# videoselector_2_0v.net
KiCad netlist of a schematic drawn in EAGLE
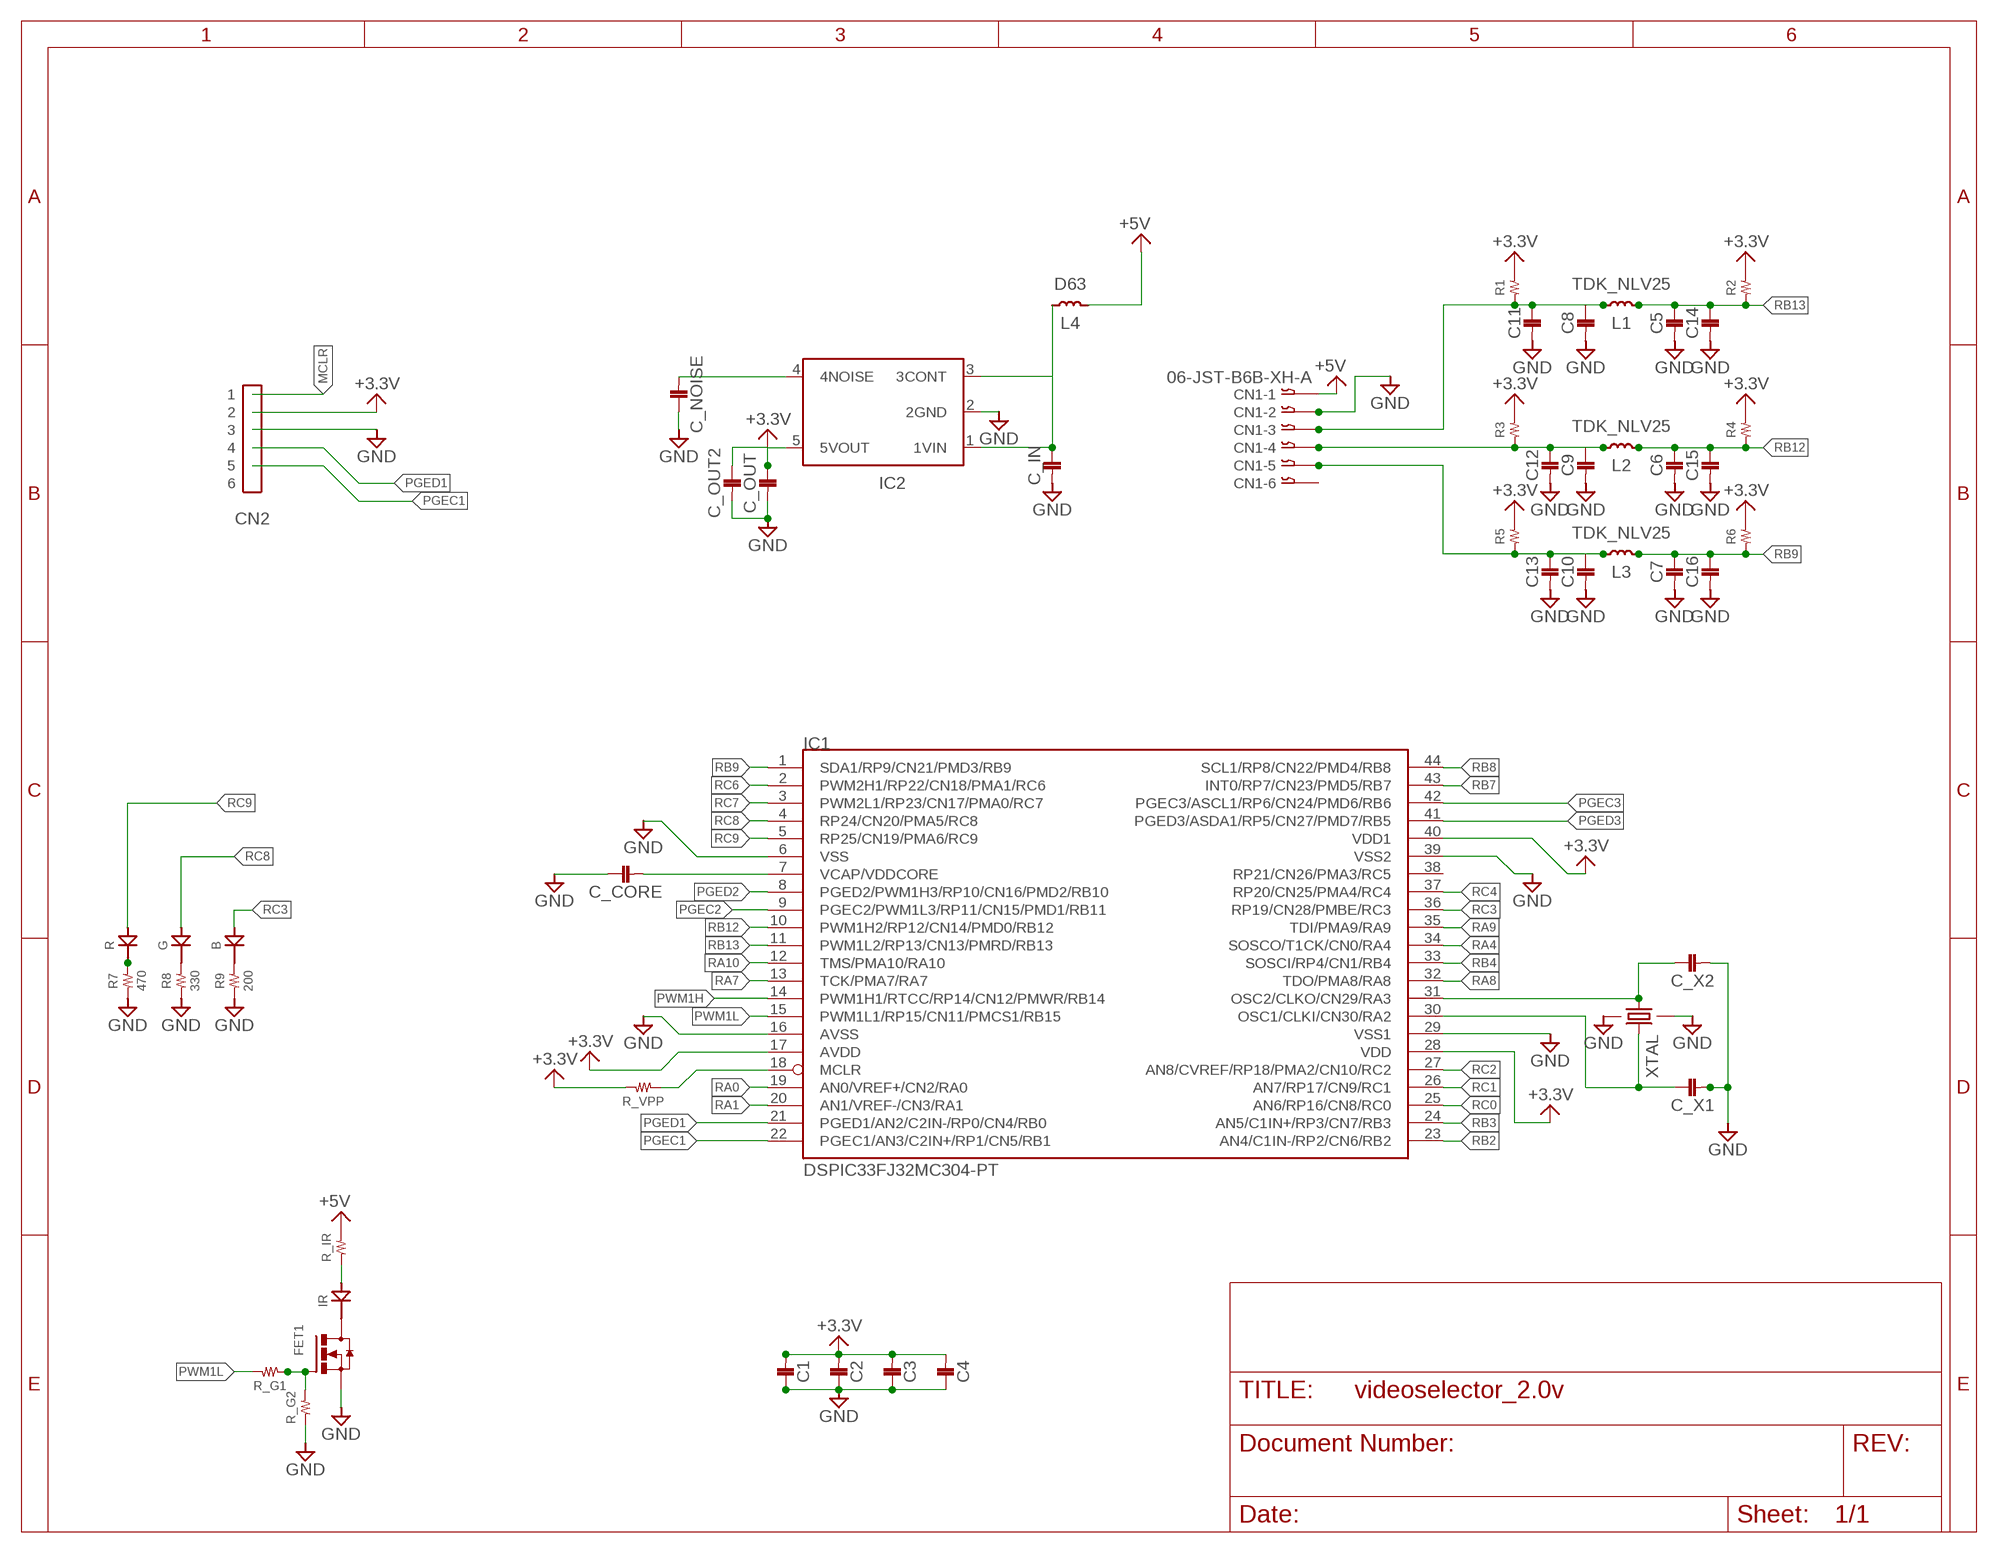
[diagram p0: schematic, sheet 1]

(export (version "E")
  (design (tool "Eeschema 10.0.6"))
  (components
    (comp (ref "B")
      (value "CHIPLED")
      (footprint "eagle-import:1608")
      (libsource (lib "eagle-import") (part "CHIPLED"))
    )
    (comp (ref "C1")
      (value "1608")
      (footprint "eagle-import:1608")
      (libsource (lib "eagle-import") (part "1608"))
    )
    (comp (ref "C2")
      (value "1608")
      (footprint "eagle-import:1608")
      (libsource (lib "eagle-import") (part "1608"))
    )
    (comp (ref "C3")
      (value "1608")
      (footprint "eagle-import:1608")
      (libsource (lib "eagle-import") (part "1608"))
    )
    (comp (ref "C4")
      (value "1608")
      (footprint "eagle-import:1608")
      (libsource (lib "eagle-import") (part "1608"))
    )
    (comp (ref "C5")
      (value "1608")
      (footprint "eagle-import:1608")
      (libsource (lib "eagle-import") (part "1608"))
    )
    (comp (ref "C6")
      (value "1608")
      (footprint "eagle-import:1608")
      (libsource (lib "eagle-import") (part "1608"))
    )
    (comp (ref "C7")
      (value "1608")
      (footprint "eagle-import:1608")
      (libsource (lib "eagle-import") (part "1608"))
    )
    (comp (ref "C8")
      (value "1608")
      (footprint "eagle-import:1608")
      (libsource (lib "eagle-import") (part "1608"))
    )
    (comp (ref "C9")
      (value "1608")
      (footprint "eagle-import:1608")
      (libsource (lib "eagle-import") (part "1608"))
    )
    (comp (ref "C10")
      (value "1608")
      (footprint "eagle-import:1608")
      (libsource (lib "eagle-import") (part "1608"))
    )
    (comp (ref "C11")
      (value "3225")
      (footprint "eagle-import:3225")
      (libsource (lib "eagle-import") (part "3225"))
    )
    (comp (ref "C12")
      (value "3225")
      (footprint "eagle-import:3225")
      (libsource (lib "eagle-import") (part "3225"))
    )
    (comp (ref "C13")
      (value "3225")
      (footprint "eagle-import:3225")
      (libsource (lib "eagle-import") (part "3225"))
    )
    (comp (ref "C14")
      (value "3225")
      (footprint "eagle-import:3225")
      (libsource (lib "eagle-import") (part "3225"))
    )
    (comp (ref "C15")
      (value "3225")
      (footprint "eagle-import:3225")
      (libsource (lib "eagle-import") (part "3225"))
    )
    (comp (ref "C16")
      (value "3225")
      (footprint "eagle-import:3225")
      (libsource (lib "eagle-import") (part "3225"))
    )
    (comp (ref "CN1")
      (value "06-JST-B6B-XH-A")
      (footprint "eagle-import:B6B-XH")
      (libsource (lib "eagle-import") (part "06-JST-B6B-XH-A"))
    )
    (comp (ref "CN2")
      (value "PIN_HEADER_6")
      (footprint "eagle-import:PIN_HEADER_6")
      (libsource (lib "eagle-import") (part "PIN_HEADER_6"))
    )
    (comp (ref "C_CORE")
      (value "2012")
      (footprint "eagle-import:2012")
      (libsource (lib "eagle-import") (part "2012"))
    )
    (comp (ref "C_IN")
      (value "1608")
      (footprint "eagle-import:1608")
      (libsource (lib "eagle-import") (part "1608"))
    )
    (comp (ref "C_NOISE")
      (value "1608")
      (footprint "eagle-import:1608")
      (libsource (lib "eagle-import") (part "1608"))
    )
    (comp (ref "C_OUT")
      (value "1608")
      (footprint "eagle-import:1608")
      (libsource (lib "eagle-import") (part "1608"))
    )
    (comp (ref "C_OUT2")
      (value "2012")
      (footprint "eagle-import:2012")
      (libsource (lib "eagle-import") (part "2012"))
    )
    (comp (ref "C_X1")
      (value "1608")
      (footprint "eagle-import:1608")
      (libsource (lib "eagle-import") (part "1608"))
    )
    (comp (ref "C_X2")
      (value "1608")
      (footprint "eagle-import:1608")
      (libsource (lib "eagle-import") (part "1608"))
    )
    (comp (ref "FET1")
      (value "ＩＲＬＭＬ６３４４")
      (footprint "eagle-import:SOT23")
      (libsource (lib "eagle-import") (part "ＩＲＬＭＬ６３４４"))
    )
    (comp (ref "G")
      (value "CHIPLED")
      (footprint "eagle-import:1608")
      (libsource (lib "eagle-import") (part "CHIPLED"))
    )
    (comp (ref "IC1")
      (value "DSPIC33FJ32MC304-PT")
      (footprint "eagle-import:TQFP44")
      (libsource (lib "eagle-import") (part "DSPIC33FJ32MC304-PT"))
    )
    (comp (ref "IC2")
      (value "TAR5SB")
      (footprint "eagle-import:SSOP5-P-0.95")
      (libsource (lib "eagle-import") (part "TAR5SB"))
    )
    (comp (ref "IR")
      (value "5MMLED")
      (footprint "eagle-import:5MM")
      (libsource (lib "eagle-import") (part "5MMLED"))
    )
    (comp (ref "L1")
      (value "TDK_NLV25")
      (footprint "eagle-import:TDK_NLV")
      (libsource (lib "eagle-import") (part "TDK_NLV25"))
    )
    (comp (ref "L2")
      (value "TDK_NLV25")
      (footprint "eagle-import:TDK_NLV")
      (libsource (lib "eagle-import") (part "TDK_NLV25"))
    )
    (comp (ref "L3")
      (value "TDK_NLV25")
      (footprint "eagle-import:TDK_NLV")
      (libsource (lib "eagle-import") (part "TDK_NLV25"))
    )
    (comp (ref "L4")
      (value "D63")
      (footprint "eagle-import:TOKO")
      (libsource (lib "eagle-import") (part "D63"))
    )
    (comp (ref "R")
      (value "CHIPLED")
      (footprint "eagle-import:1608")
      (libsource (lib "eagle-import") (part "CHIPLED"))
    )
    (comp (ref "R1")
      (value "RESISTOR__SMD")
      (footprint "eagle-import:1608")
      (libsource (lib "eagle-import") (part "RESISTOR__SMD"))
    )
    (comp (ref "R2")
      (value "RESISTOR__SMD")
      (footprint "eagle-import:1608")
      (libsource (lib "eagle-import") (part "RESISTOR__SMD"))
    )
    (comp (ref "R3")
      (value "RESISTOR__SMD")
      (footprint "eagle-import:1608")
      (libsource (lib "eagle-import") (part "RESISTOR__SMD"))
    )
    (comp (ref "R4")
      (value "RESISTOR__SMD")
      (footprint "eagle-import:1608")
      (libsource (lib "eagle-import") (part "RESISTOR__SMD"))
    )
    (comp (ref "R5")
      (value "RESISTOR__SMD")
      (footprint "eagle-import:1608")
      (libsource (lib "eagle-import") (part "RESISTOR__SMD"))
    )
    (comp (ref "R6")
      (value "RESISTOR__SMD")
      (footprint "eagle-import:1608")
      (libsource (lib "eagle-import") (part "RESISTOR__SMD"))
    )
    (comp (ref "R7")
      (value "470")
      (footprint "eagle-import:1608")
      (libsource (lib "eagle-import") (part "RESISTOR__SMD"))
    )
    (comp (ref "R8")
      (value "330")
      (footprint "eagle-import:1608")
      (libsource (lib "eagle-import") (part "RESISTOR__SMD"))
    )
    (comp (ref "R9")
      (value "200")
      (footprint "eagle-import:1608")
      (libsource (lib "eagle-import") (part "RESISTOR__SMD"))
    )
    (comp (ref "R_G1")
      (value "RESISTOR__SMD")
      (footprint "eagle-import:1608")
      (libsource (lib "eagle-import") (part "RESISTOR__SMD"))
    )
    (comp (ref "R_G2")
      (value "RESISTOR__SMD")
      (footprint "eagle-import:1608")
      (libsource (lib "eagle-import") (part "RESISTOR__SMD"))
    )
    (comp (ref "R_IR")
      (value "RESISTOR__SMD")
      (footprint "eagle-import:1608")
      (libsource (lib "eagle-import") (part "RESISTOR__SMD"))
    )
    (comp (ref "R_VPP")
      (value "RESISTOR__SMD")
      (footprint "eagle-import:1608")
      (libsource (lib "eagle-import") (part "RESISTOR__SMD"))
    )
    (comp (ref "XTAL")
      (value "FA-238")
      (footprint "eagle-import:FA-238")
      (libsource (lib "eagle-import") (part "FA-238"))
    )
  )
  (nets
    (net (code "1") (name "+3.3V") (class "Default")
      (node (ref "C1") (pin "P$2") (pinfunction "2_P$2") (pintype "passive"))
      (node (ref "C2") (pin "P$2") (pinfunction "2_P$2") (pintype "passive"))
      (node (ref "C3") (pin "P$2") (pinfunction "2_P$2") (pintype "passive"))
      (node (ref "C4") (pin "P$2") (pinfunction "2_P$2") (pintype "passive"))
      (node (ref "CN2") (pin "2") (pinfunction "2_2") (pintype "bidirectional"))
      (node (ref "C_OUT") (pin "P$1") (pinfunction "1_P$1") (pintype "passive"))
      (node (ref "C_OUT2") (pin "1") (pinfunction "1_1") (pintype "passive"))
      (node (ref "IC1") (pin "17") (pinfunction "AVDD_17") (pintype "power_in"))
      (node (ref "IC1") (pin "28") (pinfunction "VDD_28") (pintype "power_in"))
      (node (ref "IC1") (pin "40") (pinfunction "VDD1_40") (pintype "power_in"))
      (node (ref "IC2") (pin "5") (pinfunction "5VOUT_5") (pintype "bidirectional"))
      (node (ref "R1") (pin "2") (pinfunction "P$2_2") (pintype "passive"))
      (node (ref "R2") (pin "2") (pinfunction "P$2_2") (pintype "passive"))
      (node (ref "R3") (pin "2") (pinfunction "P$2_2") (pintype "passive"))
      (node (ref "R4") (pin "2") (pinfunction "P$2_2") (pintype "passive"))
      (node (ref "R5") (pin "2") (pinfunction "P$2_2") (pintype "passive"))
      (node (ref "R6") (pin "2") (pinfunction "P$2_2") (pintype "passive"))
      (node (ref "R_VPP") (pin "2") (pinfunction "P$2_2") (pintype "passive"))
    )
    (net (code "2") (name "+5V") (class "Default")
      (node (ref "CN1") (pin "P$1") (pinfunction "1_P$1") (pintype "passive"))
      (node (ref "L4") (pin "2") (pinfunction "2_2") (pintype "passive"))
      (node (ref "R_IR") (pin "2") (pinfunction "P$2_2") (pintype "passive"))
    )
    (net (code "3") (name "GND") (class "Default")
      (node (ref "C1") (pin "P$1") (pinfunction "1_P$1") (pintype "passive"))
      (node (ref "C10") (pin "P$2") (pinfunction "2_P$2") (pintype "passive"))
      (node (ref "C11") (pin "P$2") (pinfunction "2_P$2") (pintype "passive"))
      (node (ref "C12") (pin "P$2") (pinfunction "2_P$2") (pintype "passive"))
      (node (ref "C13") (pin "P$2") (pinfunction "2_P$2") (pintype "passive"))
      (node (ref "C14") (pin "P$2") (pinfunction "2_P$2") (pintype "passive"))
      (node (ref "C15") (pin "P$2") (pinfunction "2_P$2") (pintype "passive"))
      (node (ref "C16") (pin "P$2") (pinfunction "2_P$2") (pintype "passive"))
      (node (ref "C2") (pin "P$1") (pinfunction "1_P$1") (pintype "passive"))
      (node (ref "C3") (pin "P$1") (pinfunction "1_P$1") (pintype "passive"))
      (node (ref "C4") (pin "P$1") (pinfunction "1_P$1") (pintype "passive"))
      (node (ref "C5") (pin "P$2") (pinfunction "2_P$2") (pintype "passive"))
      (node (ref "C6") (pin "P$2") (pinfunction "2_P$2") (pintype "passive"))
      (node (ref "C7") (pin "P$2") (pinfunction "2_P$2") (pintype "passive"))
      (node (ref "C8") (pin "P$2") (pinfunction "2_P$2") (pintype "passive"))
      (node (ref "C9") (pin "P$2") (pinfunction "2_P$2") (pintype "passive"))
      (node (ref "CN1") (pin "P$2") (pinfunction "1_P$2") (pintype "passive"))
      (node (ref "CN2") (pin "3") (pinfunction "3_3") (pintype "bidirectional"))
      (node (ref "C_CORE") (pin "1") (pinfunction "1_1") (pintype "passive"))
      (node (ref "C_IN") (pin "P$2") (pinfunction "2_P$2") (pintype "passive"))
      (node (ref "C_NOISE") (pin "P$1") (pinfunction "1_P$1") (pintype "passive"))
      (node (ref "C_OUT") (pin "P$2") (pinfunction "2_P$2") (pintype "passive"))
      (node (ref "C_OUT2") (pin "2") (pinfunction "2_2") (pintype "passive"))
      (node (ref "C_X1") (pin "P$2") (pinfunction "2_P$2") (pintype "passive"))
      (node (ref "C_X2") (pin "P$2") (pinfunction "2_P$2") (pintype "passive"))
      (node (ref "FET1") (pin "2") (pinfunction "S_2") (pintype "passive"))
      (node (ref "IC1") (pin "16") (pinfunction "AVSS_16") (pintype "power_in"))
      (node (ref "IC1") (pin "29") (pinfunction "VSS1_29") (pintype "power_in"))
      (node (ref "IC1") (pin "39") (pinfunction "VSS2_39") (pintype "power_in"))
      (node (ref "IC1") (pin "6") (pinfunction "VSS_6") (pintype "power_in"))
      (node (ref "IC2") (pin "2") (pinfunction "2GND_2") (pintype "bidirectional"))
      (node (ref "R7") (pin "1") (pinfunction "P$1_1") (pintype "passive"))
      (node (ref "R8") (pin "1") (pinfunction "P$1_1") (pintype "passive"))
      (node (ref "R9") (pin "1") (pinfunction "P$1_1") (pintype "passive"))
      (node (ref "R_G2") (pin "1") (pinfunction "P$1_1") (pintype "passive"))
      (node (ref "XTAL") (pin "2") (pinfunction "2_2") (pintype "bidirectional"))
      (node (ref "XTAL") (pin "4") (pinfunction "4_4") (pintype "bidirectional"))
    )
    (net (code "4") (name "MCLR") (class "Default")
      (node (ref "CN2") (pin "1") (pinfunction "1_1") (pintype "bidirectional"))
      (node (ref "IC1") (pin "18") (pinfunction "MCLR_18") (pintype "input"))
      (node (ref "R_VPP") (pin "1") (pinfunction "P$1_1") (pintype "passive"))
    )
    (net (code "5") (name "Net-(B-K)") (class "Default")
      (node (ref "B") (pin "2") (pinfunction "K_2") (pintype "bidirectional"))
      (node (ref "R9") (pin "2") (pinfunction "P$2_2") (pintype "passive"))
    )
    (net (code "6") (name "Net-(C10-1)") (class "Default")
      (node (ref "C10") (pin "P$1") (pinfunction "1_P$1") (pintype "passive"))
      (node (ref "C13") (pin "P$1") (pinfunction "1_P$1") (pintype "passive"))
      (node (ref "CN1") (pin "P$5") (pinfunction "1_P$5") (pintype "passive"))
      (node (ref "L3") (pin "P$1") (pinfunction "1_P$1") (pintype "passive"))
      (node (ref "R5") (pin "1") (pinfunction "P$1_1") (pintype "passive"))
    )
    (net (code "7") (name "Net-(C11-1)") (class "Default")
      (node (ref "C11") (pin "P$1") (pinfunction "1_P$1") (pintype "passive"))
      (node (ref "C8") (pin "P$1") (pinfunction "1_P$1") (pintype "passive"))
      (node (ref "CN1") (pin "P$3") (pinfunction "1_P$3") (pintype "passive"))
      (node (ref "L1") (pin "P$1") (pinfunction "1_P$1") (pintype "passive"))
      (node (ref "R1") (pin "1") (pinfunction "P$1_1") (pintype "passive"))
    )
    (net (code "8") (name "Net-(C12-1)") (class "Default")
      (node (ref "C12") (pin "P$1") (pinfunction "1_P$1") (pintype "passive"))
      (node (ref "C9") (pin "P$1") (pinfunction "1_P$1") (pintype "passive"))
      (node (ref "CN1") (pin "P$4") (pinfunction "1_P$4") (pintype "passive"))
      (node (ref "L2") (pin "P$1") (pinfunction "1_P$1") (pintype "passive"))
      (node (ref "R3") (pin "1") (pinfunction "P$1_1") (pintype "passive"))
    )
    (net (code "9") (name "Net-(C_IN-1)") (class "Default")
      (node (ref "C_IN") (pin "P$1") (pinfunction "1_P$1") (pintype "passive"))
      (node (ref "IC2") (pin "1") (pinfunction "1VIN_1") (pintype "bidirectional"))
      (node (ref "IC2") (pin "3") (pinfunction "3CONT_3") (pintype "bidirectional"))
      (node (ref "L4") (pin "1") (pinfunction "1_1") (pintype "passive"))
    )
    (net (code "10") (name "Net-(C_NOISE-2)") (class "Default")
      (node (ref "C_NOISE") (pin "P$2") (pinfunction "2_P$2") (pintype "passive"))
      (node (ref "IC2") (pin "4") (pinfunction "4NOISE_4") (pintype "bidirectional"))
    )
    (net (code "11") (name "Net-(C_X1-1)") (class "Default")
      (node (ref "C_X1") (pin "P$1") (pinfunction "1_P$1") (pintype "passive"))
      (node (ref "IC1") (pin "30") (pinfunction "OSC1/CLKI/CN30/RA2_30") (pintype "bidirectional"))
      (node (ref "XTAL") (pin "3") (pinfunction "3_3") (pintype "passive"))
    )
    (net (code "12") (name "Net-(C_X2-1)") (class "Default")
      (node (ref "C_X2") (pin "P$1") (pinfunction "1_P$1") (pintype "passive"))
      (node (ref "IC1") (pin "31") (pinfunction "OSC2/CLKO/CN29/RA3_31") (pintype "bidirectional"))
      (node (ref "XTAL") (pin "1") (pinfunction "1_1") (pintype "passive"))
    )
    (net (code "13") (name "Net-(FET1-D)") (class "Default")
      (node (ref "FET1") (pin "3") (pinfunction "D_3") (pintype "passive"))
      (node (ref "IR") (pin "K") (pinfunction "K_K") (pintype "bidirectional"))
    )
    (net (code "14") (name "Net-(FET1-G)") (class "Default")
      (node (ref "FET1") (pin "1") (pinfunction "G_1") (pintype "passive"))
      (node (ref "R_G1") (pin "1") (pinfunction "P$1_1") (pintype "passive"))
      (node (ref "R_G2") (pin "2") (pinfunction "P$2_2") (pintype "passive"))
    )
    (net (code "15") (name "Net-(G-K)") (class "Default")
      (node (ref "G") (pin "2") (pinfunction "K_2") (pintype "bidirectional"))
      (node (ref "R8") (pin "2") (pinfunction "P$2_2") (pintype "passive"))
    )
    (net (code "16") (name "Net-(IC1-VCAP{slash}VDDCORE)") (class "Default")
      (node (ref "C_CORE") (pin "2") (pinfunction "2_2") (pintype "passive"))
      (node (ref "IC1") (pin "7") (pinfunction "VCAP/VDDCORE_7") (pintype "power_in"))
    )
    (net (code "17") (name "Net-(R-K)") (class "Default")
      (node (ref "R") (pin "2") (pinfunction "K_2") (pintype "bidirectional"))
      (node (ref "R7") (pin "2") (pinfunction "P$2_2") (pintype "passive"))
    )
    (net (code "18") (name "Net-(R_IR-P$1)") (class "Default")
      (node (ref "IR") (pin "A") (pinfunction "A_A") (pintype "bidirectional"))
      (node (ref "R_IR") (pin "1") (pinfunction "P$1_1") (pintype "passive"))
    )
    (net (code "19") (name "PGEC1") (class "Default")
      (node (ref "CN2") (pin "5") (pinfunction "5_5") (pintype "bidirectional"))
      (node (ref "IC1") (pin "22") (pinfunction "PGEC1/AN3/C2IN+/RP1/CN5/RB1_22") (pintype "bidirectional"))
    )
    (net (code "20") (name "PGEC2") (class "Default")
      (node (ref "IC1") (pin "9") (pinfunction "PGEC2/PWM1L3/RP11/CN15/PMD1/RB11_9") (pintype "bidirectional"))
    )
    (net (code "21") (name "PGEC3") (class "Default")
      (node (ref "IC1") (pin "42") (pinfunction "PGEC3/ASCL1/RP6/CN24/PMD6/RB6_42") (pintype "bidirectional"))
    )
    (net (code "22") (name "PGED1") (class "Default")
      (node (ref "CN2") (pin "4") (pinfunction "4_4") (pintype "bidirectional"))
      (node (ref "IC1") (pin "21") (pinfunction "PGED1/AN2/C2IN-/RP0/CN4/RB0_21") (pintype "bidirectional"))
    )
    (net (code "23") (name "PGED2") (class "Default")
      (node (ref "IC1") (pin "8") (pinfunction "PGED2/PWM1H3/RP10/CN16/PMD2/RB10_8") (pintype "bidirectional"))
    )
    (net (code "24") (name "PGED3") (class "Default")
      (node (ref "IC1") (pin "41") (pinfunction "PGED3/ASDA1/RP5/CN27/PMD7/RB5_41") (pintype "bidirectional"))
    )
    (net (code "25") (name "PWM1H") (class "Default")
      (node (ref "IC1") (pin "14") (pinfunction "PWM1H1/RTCC/RP14/CN12/PMWR/RB14_14") (pintype "bidirectional"))
    )
    (net (code "26") (name "PWM1L") (class "Default")
      (node (ref "IC1") (pin "15") (pinfunction "PWM1L1/RP15/CN11/PMCS1/RB15_15") (pintype "bidirectional"))
      (node (ref "R_G1") (pin "2") (pinfunction "P$2_2") (pintype "passive"))
    )
    (net (code "27") (name "RA0") (class "Default")
      (node (ref "IC1") (pin "19") (pinfunction "AN0/VREF+/CN2/RA0_19") (pintype "bidirectional"))
    )
    (net (code "28") (name "RA1") (class "Default")
      (node (ref "IC1") (pin "20") (pinfunction "AN1/VREF-/CN3/RA1_20") (pintype "bidirectional"))
    )
    (net (code "29") (name "RA4") (class "Default")
      (node (ref "IC1") (pin "34") (pinfunction "SOSCO/T1CK/CN0/RA4_34") (pintype "bidirectional"))
    )
    (net (code "30") (name "RA7") (class "Default")
      (node (ref "IC1") (pin "13") (pinfunction "TCK/PMA7/RA7_13") (pintype "bidirectional"))
    )
    (net (code "31") (name "RA8") (class "Default")
      (node (ref "IC1") (pin "32") (pinfunction "TDO/PMA8/RA8_32") (pintype "bidirectional"))
    )
    (net (code "32") (name "RA9") (class "Default")
      (node (ref "IC1") (pin "35") (pinfunction "TDI/PMA9/RA9_35") (pintype "bidirectional"))
    )
    (net (code "33") (name "RA10") (class "Default")
      (node (ref "IC1") (pin "12") (pinfunction "TMS/PMA10/RA10_12") (pintype "bidirectional"))
    )
    (net (code "34") (name "RB2") (class "Default")
      (node (ref "IC1") (pin "23") (pinfunction "AN4/C1IN-/RP2/CN6/RB2_23") (pintype "bidirectional"))
    )
    (net (code "35") (name "RB3") (class "Default")
      (node (ref "IC1") (pin "24") (pinfunction "AN5/C1IN+/RP3/CN7/RB3_24") (pintype "bidirectional"))
    )
    (net (code "36") (name "RB4") (class "Default")
      (node (ref "IC1") (pin "33") (pinfunction "SOSCI/RP4/CN1/RB4_33") (pintype "bidirectional"))
    )
    (net (code "37") (name "RB7") (class "Default")
      (node (ref "IC1") (pin "43") (pinfunction "INT0/RP7/CN23/PMD5/RB7_43") (pintype "bidirectional"))
    )
    (net (code "38") (name "RB8") (class "Default")
      (node (ref "IC1") (pin "44") (pinfunction "SCL1/RP8/CN22/PMD4/RB8_44") (pintype "bidirectional"))
    )
    (net (code "39") (name "RB9") (class "Default")
      (node (ref "C16") (pin "P$1") (pinfunction "1_P$1") (pintype "passive"))
      (node (ref "C7") (pin "P$1") (pinfunction "1_P$1") (pintype "passive"))
      (node (ref "IC1") (pin "1") (pinfunction "SDA1/RP9/CN21/PMD3/RB9_1") (pintype "bidirectional"))
      (node (ref "L3") (pin "P$2") (pinfunction "2_P$2") (pintype "passive"))
      (node (ref "R6") (pin "1") (pinfunction "P$1_1") (pintype "passive"))
    )
    (net (code "40") (name "RB12") (class "Default")
      (node (ref "C15") (pin "P$1") (pinfunction "1_P$1") (pintype "passive"))
      (node (ref "C6") (pin "P$1") (pinfunction "1_P$1") (pintype "passive"))
      (node (ref "IC1") (pin "10") (pinfunction "PWM1H2/RP12/CN14/PMD0/RB12_10") (pintype "bidirectional"))
      (node (ref "L2") (pin "P$2") (pinfunction "2_P$2") (pintype "passive"))
      (node (ref "R4") (pin "1") (pinfunction "P$1_1") (pintype "passive"))
    )
    (net (code "41") (name "RB13") (class "Default")
      (node (ref "C14") (pin "P$1") (pinfunction "1_P$1") (pintype "passive"))
      (node (ref "C5") (pin "P$1") (pinfunction "1_P$1") (pintype "passive"))
      (node (ref "IC1") (pin "11") (pinfunction "PWM1L2/RP13/CN13/PMRD/RB13_11") (pintype "bidirectional"))
      (node (ref "L1") (pin "P$2") (pinfunction "2_P$2") (pintype "passive"))
      (node (ref "R2") (pin "1") (pinfunction "P$1_1") (pintype "passive"))
    )
    (net (code "42") (name "RC0") (class "Default")
      (node (ref "IC1") (pin "25") (pinfunction "AN6/RP16/CN8/RC0_25") (pintype "bidirectional"))
    )
    (net (code "43") (name "RC1") (class "Default")
      (node (ref "IC1") (pin "26") (pinfunction "AN7/RP17/CN9/RC1_26") (pintype "bidirectional"))
    )
    (net (code "44") (name "RC2") (class "Default")
      (node (ref "IC1") (pin "27") (pinfunction "AN8/CVREF/RP18/PMA2/CN10/RC2_27") (pintype "bidirectional"))
    )
    (net (code "45") (name "RC3") (class "Default")
      (node (ref "B") (pin "1") (pinfunction "A_1") (pintype "bidirectional"))
      (node (ref "IC1") (pin "36") (pinfunction "RP19/CN28/PMBE/RC3_36") (pintype "bidirectional"))
    )
    (net (code "46") (name "RC4") (class "Default")
      (node (ref "IC1") (pin "37") (pinfunction "RP20/CN25/PMA4/RC4_37") (pintype "bidirectional"))
    )
    (net (code "47") (name "RC6") (class "Default")
      (node (ref "IC1") (pin "2") (pinfunction "PWM2H1/RP22/CN18/PMA1/RC6_2") (pintype "bidirectional"))
    )
    (net (code "48") (name "RC7") (class "Default")
      (node (ref "IC1") (pin "3") (pinfunction "PWM2L1/RP23/CN17/PMA0/RC7_3") (pintype "bidirectional"))
    )
    (net (code "49") (name "RC8") (class "Default")
      (node (ref "G") (pin "1") (pinfunction "A_1") (pintype "bidirectional"))
      (node (ref "IC1") (pin "4") (pinfunction "RP24/CN20/PMA5/RC8_4") (pintype "bidirectional"))
    )
    (net (code "50") (name "RC9") (class "Default")
      (node (ref "IC1") (pin "5") (pinfunction "RP25/CN19/PMA6/RC9_5") (pintype "bidirectional"))
      (node (ref "R") (pin "1") (pinfunction "A_1") (pintype "bidirectional"))
    )
    (net (code "51") (name "unconnected-(CN1F-1-PadP$6)") (class "Default")
      (node (ref "CN1") (pin "P$6") (pinfunction "1_P$6") (pintype "passive"))
    )
    (net (code "52") (name "unconnected-(CN2-Pad6)") (class "Default")
      (node (ref "CN2") (pin "6") (pinfunction "6_6") (pintype "bidirectional"))
    )
    (net (code "53") (name "unconnected-(IC1-RP21{slash}CN26{slash}PMA3{slash}RC5-Pad38)") (class "Default")
      (node (ref "IC1") (pin "38") (pinfunction "RP21/CN26/PMA3/RC5_38") (pintype "bidirectional"))
    )
  )
)
